# Starter.net
KiCad netlist of a schematic drawn in EAGLE
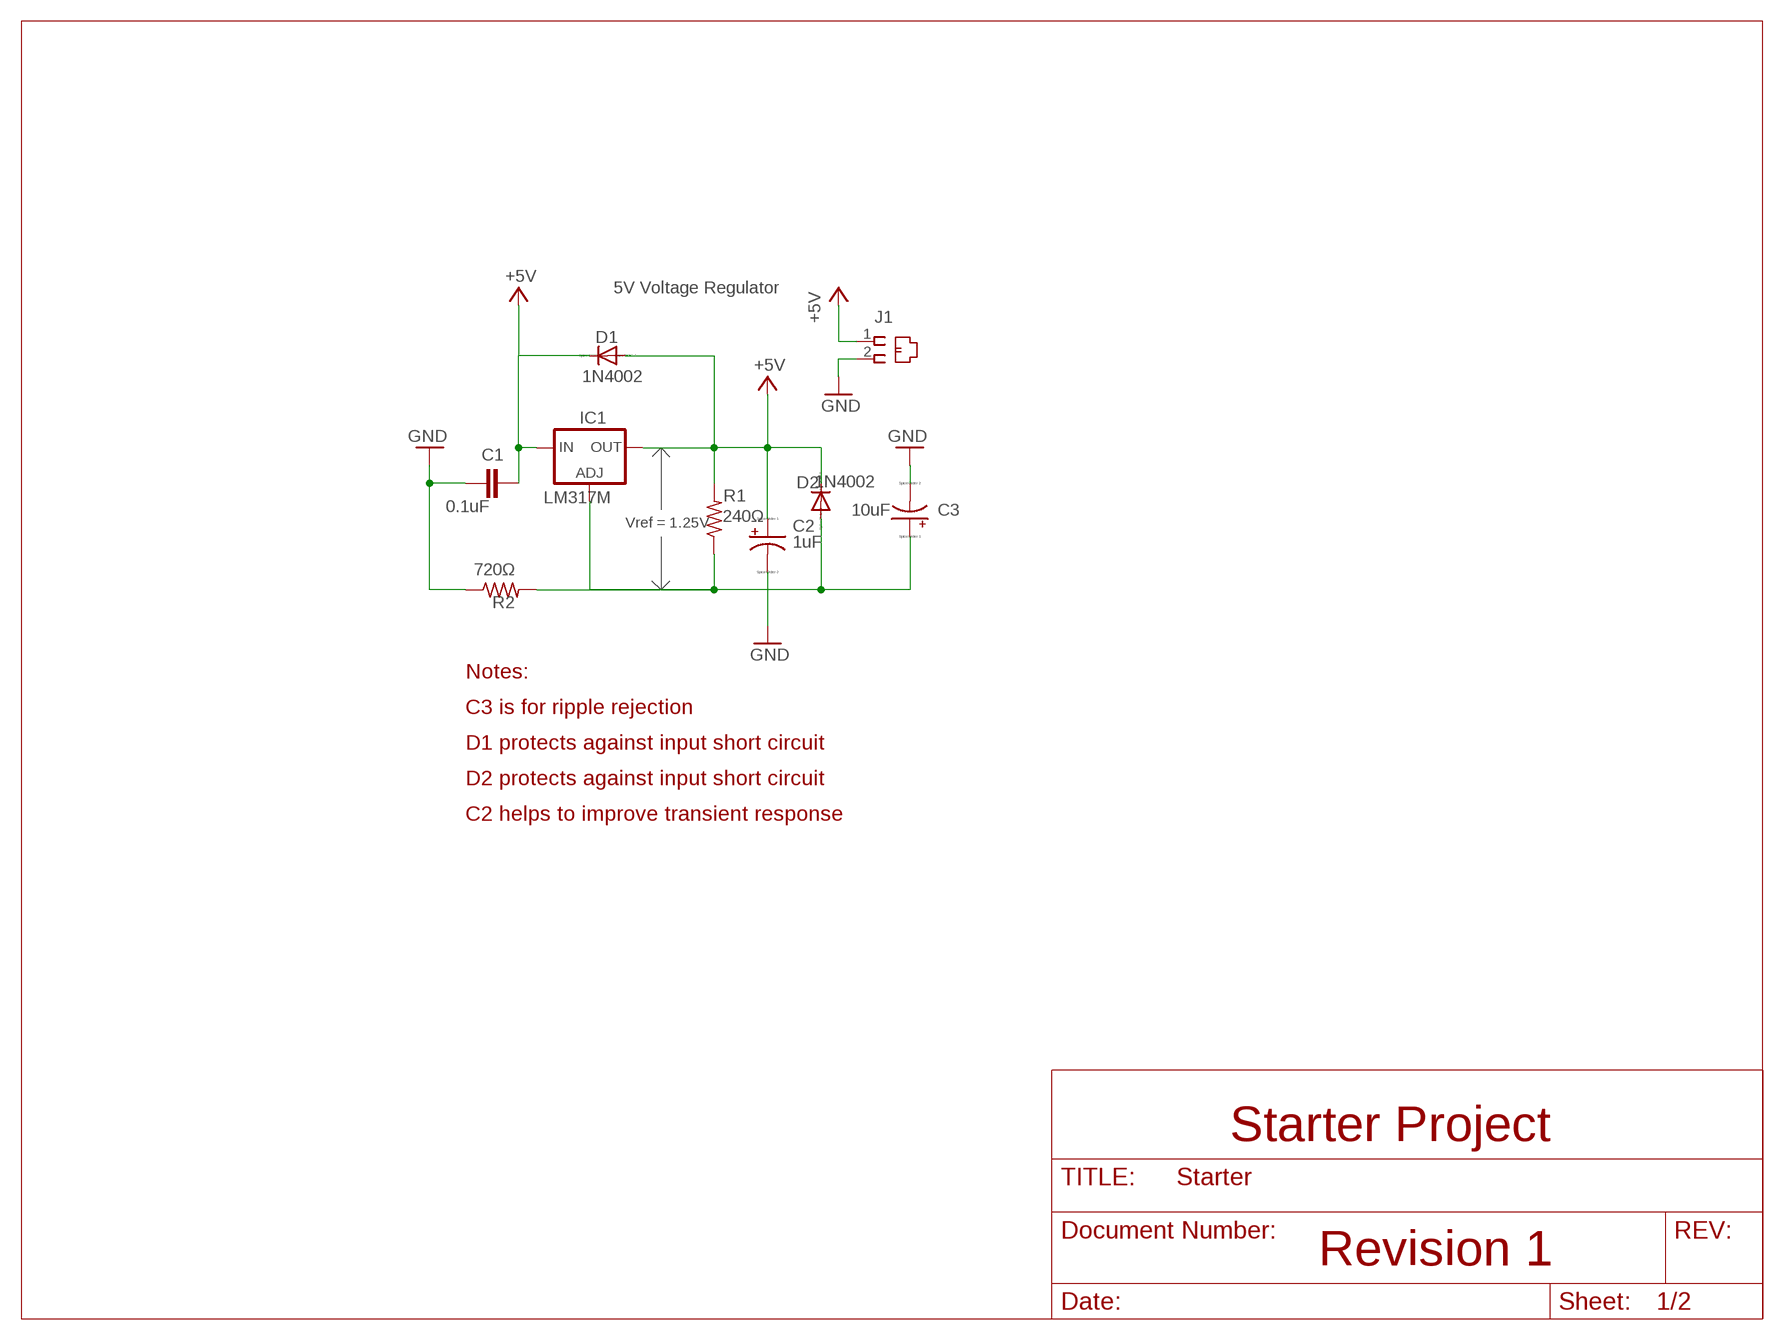
[diagram p0: schematic, sheet 1]

(export (version "E")
  (design (tool "Eeschema 10.0.6"))
  (components
    (comp (ref "C1")
      (value "0.1uF")
      (footprint "eagle-import:C075-052X106")
      (libsource (lib "eagle-import") (part "C-EU075-052X106"))
    )
    (comp (ref "C2")
      (value "1uF")
      (footprint "eagle-import:085CS_1AR")
      (libsource (lib "eagle-import") (part "CPOL-US085CS-1AR"))
    )
    (comp (ref "C3")
      (value "10uF")
      (footprint "eagle-import:085CS_1AR")
      (libsource (lib "eagle-import") (part "CPOL-US085CS-1AR"))
    )
    (comp (ref "D1")
      (value "1N4002")
      (footprint "eagle-import:DO41-10")
      (libsource (lib "eagle-import") (part "1N4004"))
    )
    (comp (ref "D2")
      (value "1N4002")
      (footprint "eagle-import:DO41-10")
      (libsource (lib "eagle-import") (part "1N4004"))
    )
    (comp (ref "IC1")
      (value "LM317MBSTT3")
      (footprint "eagle-import:SOT223")
      (fields (field (name "PARTNUMBER") "LM317M"))
      (libsource (lib "eagle-import") (part "LM317?MBSTT3"))
    )
    (comp (ref "J1")
      (value "520250-1")
      (footprint "eagle-import:520250-1")
      (libsource (lib "eagle-import") (part "520250-1"))
    )
    (comp (ref "R1")
      (value "240Ω")
      (footprint "eagle-import:M0805")
      (libsource (lib "eagle-import") (part "R-US_M0805"))
    )
    (comp (ref "R2")
      (value "720Ω")
      (footprint "eagle-import:M0805")
      (libsource (lib "eagle-import") (part "R-US_M0805"))
    )
  )
  (nets
    (net (code "1") (name "+5V") (class "Default")
      (node (ref "C1") (pin "1") (pinfunction "1_1") (pintype "passive"))
      (node (ref "C2") (pin "+") (pinfunction "+_+") (pintype "passive"))
      (node (ref "D1") (pin "A") (pinfunction "A_A") (pintype "passive"))
      (node (ref "D1") (pin "C") (pinfunction "C_C") (pintype "passive"))
      (node (ref "D2") (pin "C") (pinfunction "C_C") (pintype "passive"))
      (node (ref "IC1") (pin "3") (pinfunction "IN_3") (pintype "input"))
      (node (ref "IC1") (pin "4") (pinfunction "OUT_4") (pintype "passive"))
      (node (ref "J1") (pin "1") (pinfunction "1_1") (pintype "passive"))
      (node (ref "R1") (pin "2") (pinfunction "2_2") (pintype "passive"))
    )
    (net (code "2") (name "GND") (class "Default")
      (node (ref "C1") (pin "2") (pinfunction "2_2") (pintype "passive"))
      (node (ref "C2") (pin "-") (pinfunction "-_-") (pintype "passive"))
      (node (ref "C3") (pin "-") (pinfunction "-_-") (pintype "passive"))
      (node (ref "J1") (pin "2") (pinfunction "2_2") (pintype "passive"))
      (node (ref "R2") (pin "1") (pinfunction "1_1") (pintype "passive"))
    )
    (net (code "3") (name "Net-(IC1-ADJ)") (class "Default")
      (node (ref "C3") (pin "+") (pinfunction "+_+") (pintype "passive"))
      (node (ref "D2") (pin "A") (pinfunction "A_A") (pintype "passive"))
      (node (ref "IC1") (pin "1") (pinfunction "ADJ_1") (pintype "input"))
      (node (ref "R1") (pin "1") (pinfunction "1_1") (pintype "passive"))
      (node (ref "R2") (pin "2") (pinfunction "2_2") (pintype "passive"))
    )
  )
)
